# DriverBoard.net
KiCad netlist of a schematic drawn in EAGLE
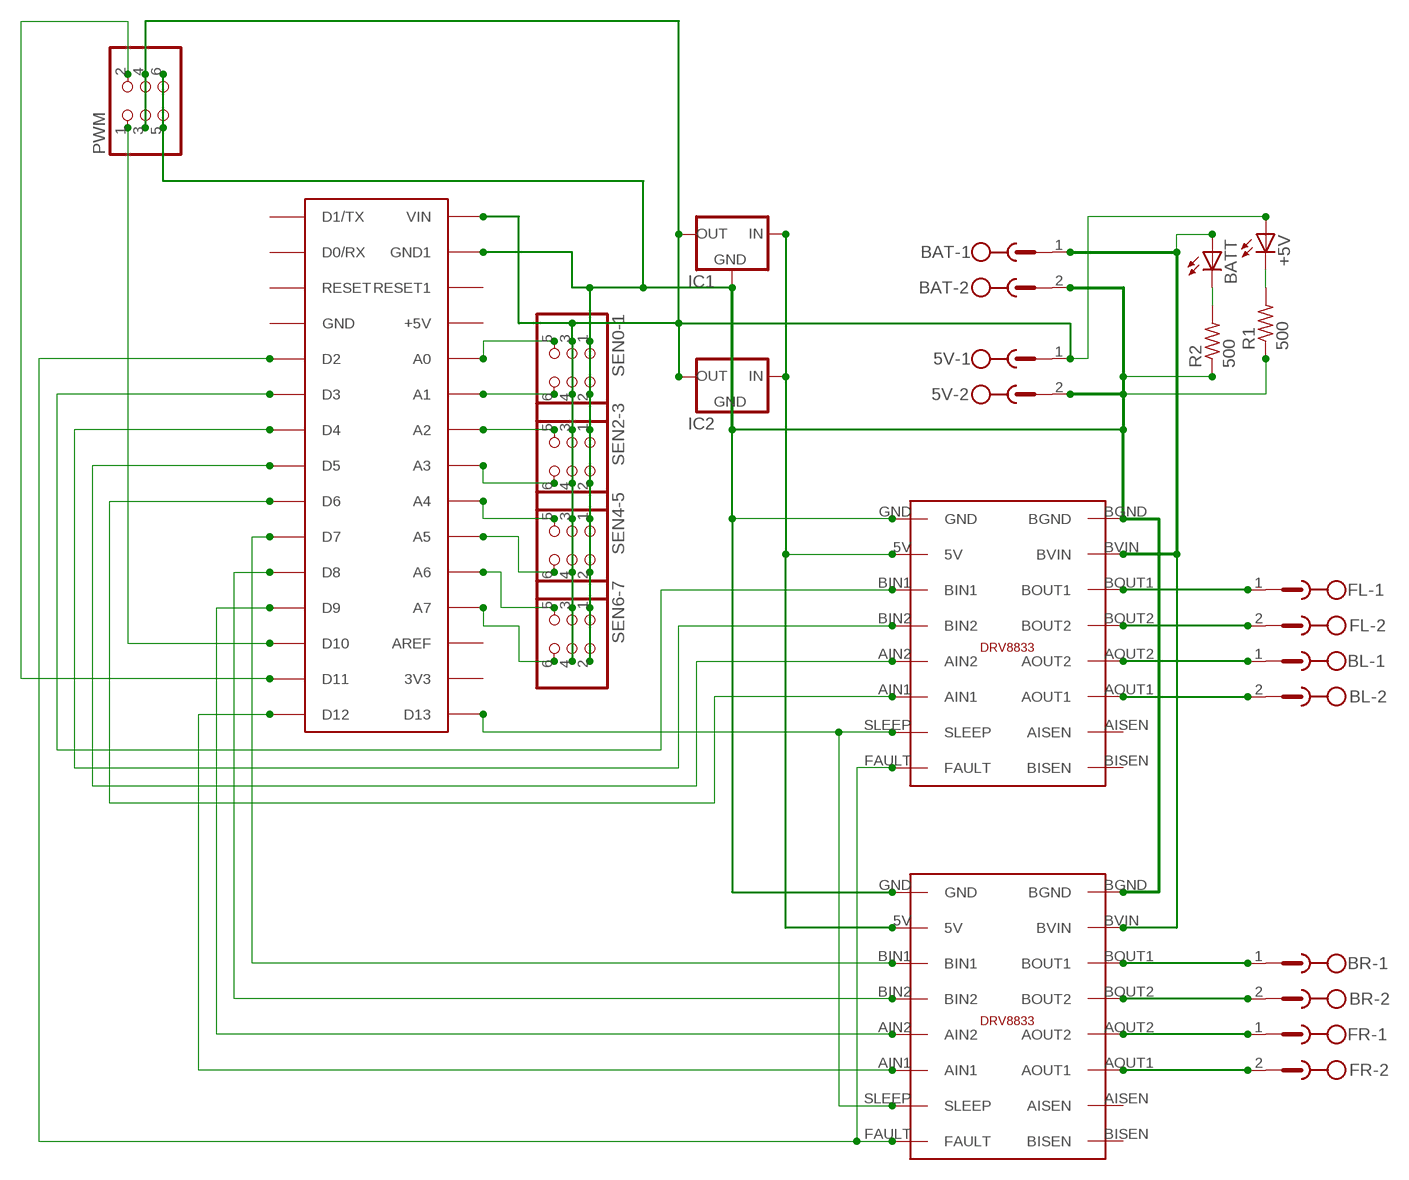
[diagram p0: schematic, sheet 1]

(export (version "E")
  (design (tool "Eeschema 10.0.6"))
  (components
    (comp (ref "+5V")
      (value "LED5MM")
      (footprint "eagle-import:LED5MM")
      (libsource (lib "eagle-import") (part "LED5MM"))
    )
    (comp (ref "5V")
      (value "MSTBV2")
      (footprint "eagle-import:MSTBV2")
      (libsource (lib "eagle-import") (part "MSTBV2"))
    )
    (comp (ref "BAT")
      (value "MSTBV2")
      (footprint "eagle-import:MSTBV2")
      (libsource (lib "eagle-import") (part "MSTBV2"))
    )
    (comp (ref "BATT")
      (value "LED5MM")
      (footprint "eagle-import:LED5MM")
      (libsource (lib "eagle-import") (part "LED5MM"))
    )
    (comp (ref "BL")
      (value "MSTBV2")
      (footprint "eagle-import:MSTBV2")
      (libsource (lib "eagle-import") (part "MSTBV2"))
    )
    (comp (ref "BR")
      (value "MSTBV2")
      (footprint "eagle-import:MSTBV2")
      (libsource (lib "eagle-import") (part "MSTBV2"))
    )
    (comp (ref "FL")
      (value "MSTBV2")
      (footprint "eagle-import:MSTBV2")
      (libsource (lib "eagle-import") (part "MSTBV2"))
    )
    (comp (ref "FR")
      (value "MSTBV2")
      (footprint "eagle-import:MSTBV2")
      (libsource (lib "eagle-import") (part "MSTBV2"))
    )
    (comp (ref "IC1")
      (value "78XXS")
      (footprint "eagle-import:78XXS")
      (libsource (lib "eagle-import") (part "78XXS"))
    )
    (comp (ref "IC2")
      (value "78XXS")
      (footprint "eagle-import:78XXS")
      (libsource (lib "eagle-import") (part "78XXS"))
    )
    (comp (ref "PWM")
      (value "PINHD-2X3")
      (footprint "eagle-import:2X03")
      (libsource (lib "eagle-import") (part "PINHD-2X3"))
    )
    (comp (ref "R1")
      (value "500")
      (footprint "eagle-import:0207_10")
      (libsource (lib "eagle-import") (part "R-US_0207/10"))
    )
    (comp (ref "R2")
      (value "500")
      (footprint "eagle-import:0207_10")
      (libsource (lib "eagle-import") (part "R-US_0207/10"))
    )
    (comp (ref "SEN0-1")
      (value "PINHD-2X3")
      (footprint "eagle-import:2X03")
      (libsource (lib "eagle-import") (part "PINHD-2X3"))
    )
    (comp (ref "SEN2-3")
      (value "PINHD-2X3")
      (footprint "eagle-import:2X03")
      (libsource (lib "eagle-import") (part "PINHD-2X3"))
    )
    (comp (ref "SEN4-5")
      (value "PINHD-2X3")
      (footprint "eagle-import:2X03")
      (libsource (lib "eagle-import") (part "PINHD-2X3"))
    )
    (comp (ref "SEN6-7")
      (value "PINHD-2X3")
      (footprint "eagle-import:2X03")
      (libsource (lib "eagle-import") (part "PINHD-2X3"))
    )
    (comp (ref "U$1")
      (value "ARDUINONANO")
      (footprint "eagle-import:PDIP-32")
      (libsource (lib "eagle-import") (part "ARDUINONANO"))
    )
    (comp (ref "U$2")
      (value "DRV8833")
      (footprint "eagle-import:DRV8833")
      (libsource (lib "eagle-import") (part "DRV8833"))
    )
    (comp (ref "U$3")
      (value "DRV8833")
      (footprint "eagle-import:DRV8833")
      (libsource (lib "eagle-import") (part "DRV8833"))
    )
  )
  (nets
    (net (code "1") (name "Net-(+5V-C)") (class "Default")
      (node (ref "+5V") (pin "K") (pinfunction "C_K") (pintype "passive"))
      (node (ref "R1") (pin "2") (pinfunction "2_2") (pintype "passive"))
    )
    (net (code "2") (name "Net-(5VA-SK)") (class "Default")
      (node (ref "+5V") (pin "A") (pinfunction "A_A") (pintype "passive"))
      (node (ref "5V") (pin "1") (pinfunction "SK_1") (pintype "passive"))
      (node (ref "IC1") (pin "OUT") (pinfunction "OUT_OUT") (pintype "passive"))
      (node (ref "IC2") (pin "OUT") (pinfunction "OUT_OUT") (pintype "passive"))
      (node (ref "PWM") (pin "3") (pinfunction "3_3") (pintype "passive"))
      (node (ref "PWM") (pin "4") (pinfunction "4_4") (pintype "passive"))
      (node (ref "SEN0-1") (pin "3") (pinfunction "3_3") (pintype "passive"))
      (node (ref "SEN0-1") (pin "4") (pinfunction "4_4") (pintype "passive"))
      (node (ref "SEN2-3") (pin "3") (pinfunction "3_3") (pintype "passive"))
      (node (ref "SEN2-3") (pin "4") (pinfunction "4_4") (pintype "passive"))
      (node (ref "SEN4-5") (pin "3") (pinfunction "3_3") (pintype "passive"))
      (node (ref "SEN4-5") (pin "4") (pinfunction "4_4") (pintype "passive"))
      (node (ref "SEN6-7") (pin "3") (pinfunction "3_3") (pintype "passive"))
      (node (ref "SEN6-7") (pin "4") (pinfunction "4_4") (pintype "passive"))
      (node (ref "U$1") (pin "VIN") (pinfunction "VIN_VIN") (pintype "bidirectional"))
    )
    (net (code "3") (name "Net-(5VB-SK)") (class "Default")
      (node (ref "5V") (pin "2") (pinfunction "SK_2") (pintype "passive"))
      (node (ref "BAT") (pin "2") (pinfunction "SK_2") (pintype "passive"))
      (node (ref "IC1") (pin "GND") (pinfunction "GND_GND") (pintype "input"))
      (node (ref "IC2") (pin "GND") (pinfunction "GND_GND") (pintype "input"))
      (node (ref "PWM") (pin "5") (pinfunction "5_5") (pintype "passive"))
      (node (ref "PWM") (pin "6") (pinfunction "6_6") (pintype "passive"))
      (node (ref "R1") (pin "1") (pinfunction "1_1") (pintype "passive"))
      (node (ref "R2") (pin "1") (pinfunction "1_1") (pintype "passive"))
      (node (ref "SEN0-1") (pin "1") (pinfunction "1_1") (pintype "passive"))
      (node (ref "SEN0-1") (pin "2") (pinfunction "2_2") (pintype "passive"))
      (node (ref "SEN2-3") (pin "1") (pinfunction "1_1") (pintype "passive"))
      (node (ref "SEN2-3") (pin "2") (pinfunction "2_2") (pintype "passive"))
      (node (ref "SEN4-5") (pin "1") (pinfunction "1_1") (pintype "passive"))
      (node (ref "SEN4-5") (pin "2") (pinfunction "2_2") (pintype "passive"))
      (node (ref "SEN6-7") (pin "1") (pinfunction "1_1") (pintype "passive"))
      (node (ref "SEN6-7") (pin "2") (pinfunction "2_2") (pintype "passive"))
      (node (ref "U$1") (pin "GND1") (pinfunction "GND1_GND1") (pintype "bidirectional"))
      (node (ref "U$2") (pin "BGND") (pinfunction "BGND_BGND") (pintype "bidirectional"))
      (node (ref "U$2") (pin "GND") (pinfunction "GND_GND") (pintype "bidirectional"))
      (node (ref "U$3") (pin "BGND") (pinfunction "BGND_BGND") (pintype "bidirectional"))
      (node (ref "U$3") (pin "GND") (pinfunction "GND_GND") (pintype "bidirectional"))
    )
    (net (code "4") (name "Net-(BATA-SK)") (class "Default")
      (node (ref "BAT") (pin "1") (pinfunction "SK_1") (pintype "passive"))
      (node (ref "BATT") (pin "A") (pinfunction "A_A") (pintype "passive"))
      (node (ref "U$2") (pin "BVIN") (pinfunction "BVIN_BVIN") (pintype "bidirectional"))
      (node (ref "U$3") (pin "BVIN") (pinfunction "BVIN_BVIN") (pintype "bidirectional"))
    )
    (net (code "5") (name "Net-(BATT-C)") (class "Default")
      (node (ref "BATT") (pin "K") (pinfunction "C_K") (pintype "passive"))
      (node (ref "R2") (pin "2") (pinfunction "2_2") (pintype "passive"))
    )
    (net (code "6") (name "Net-(BLA-SK)") (class "Default")
      (node (ref "BL") (pin "1") (pinfunction "SK_1") (pintype "passive"))
      (node (ref "U$2") (pin "AOUT2") (pinfunction "AOUT2_AOUT2") (pintype "bidirectional"))
    )
    (net (code "7") (name "Net-(BLB-SK)") (class "Default")
      (node (ref "BL") (pin "2") (pinfunction "SK_2") (pintype "passive"))
      (node (ref "U$2") (pin "AOUT1") (pinfunction "AOUT1_AOUT1") (pintype "bidirectional"))
    )
    (net (code "8") (name "Net-(BRA-SK)") (class "Default")
      (node (ref "BR") (pin "1") (pinfunction "SK_1") (pintype "passive"))
      (node (ref "U$3") (pin "BOUT1") (pinfunction "BOUT1_BOUT1") (pintype "bidirectional"))
    )
    (net (code "9") (name "Net-(BRB-SK)") (class "Default")
      (node (ref "BR") (pin "2") (pinfunction "SK_2") (pintype "passive"))
      (node (ref "U$3") (pin "BOUT2") (pinfunction "BOUT2_BOUT2") (pintype "bidirectional"))
    )
    (net (code "10") (name "Net-(FLA-SK)") (class "Default")
      (node (ref "FL") (pin "1") (pinfunction "SK_1") (pintype "passive"))
      (node (ref "U$2") (pin "BOUT1") (pinfunction "BOUT1_BOUT1") (pintype "bidirectional"))
    )
    (net (code "11") (name "Net-(FLB-SK)") (class "Default")
      (node (ref "FL") (pin "2") (pinfunction "SK_2") (pintype "passive"))
      (node (ref "U$2") (pin "BOUT2") (pinfunction "BOUT2_BOUT2") (pintype "bidirectional"))
    )
    (net (code "12") (name "Net-(FRA-SK)") (class "Default")
      (node (ref "FR") (pin "1") (pinfunction "SK_1") (pintype "passive"))
      (node (ref "U$3") (pin "AOUT2") (pinfunction "AOUT2_AOUT2") (pintype "bidirectional"))
    )
    (net (code "13") (name "Net-(FRB-SK)") (class "Default")
      (node (ref "FR") (pin "2") (pinfunction "SK_2") (pintype "passive"))
      (node (ref "U$3") (pin "AOUT1") (pinfunction "AOUT1_AOUT1") (pintype "bidirectional"))
    )
    (net (code "14") (name "Net-(IC1-PadIN)") (class "Default")
      (node (ref "IC1") (pin "IN") (pinfunction "IN_IN") (pintype "input"))
      (node (ref "IC2") (pin "IN") (pinfunction "IN_IN") (pintype "input"))
      (node (ref "U$2") (pin "5V") (pinfunction "5V_5V") (pintype "bidirectional"))
      (node (ref "U$3") (pin "5V") (pinfunction "5V_5V") (pintype "bidirectional"))
    )
    (net (code "15") (name "Net-(PWM-Pad1)") (class "Default")
      (node (ref "PWM") (pin "1") (pinfunction "1_1") (pintype "passive"))
      (node (ref "U$1") (pin "D10") (pinfunction "D10_D10") (pintype "bidirectional"))
    )
    (net (code "16") (name "Net-(PWM-Pad2)") (class "Default")
      (node (ref "PWM") (pin "2") (pinfunction "2_2") (pintype "passive"))
      (node (ref "U$1") (pin "D11") (pinfunction "D11_D11") (pintype "bidirectional"))
    )
    (net (code "17") (name "Net-(SEN0-1-Pad5)") (class "Default")
      (node (ref "SEN0-1") (pin "5") (pinfunction "5_5") (pintype "passive"))
      (node (ref "U$1") (pin "A0") (pinfunction "A0_A0") (pintype "bidirectional"))
    )
    (net (code "18") (name "Net-(SEN0-1-Pad6)") (class "Default")
      (node (ref "SEN0-1") (pin "6") (pinfunction "6_6") (pintype "passive"))
      (node (ref "U$1") (pin "A1") (pinfunction "A1_A1") (pintype "bidirectional"))
    )
    (net (code "19") (name "Net-(SEN2-3-Pad5)") (class "Default")
      (node (ref "SEN2-3") (pin "5") (pinfunction "5_5") (pintype "passive"))
      (node (ref "U$1") (pin "A2") (pinfunction "A2_A2") (pintype "bidirectional"))
    )
    (net (code "20") (name "Net-(SEN2-3-Pad6)") (class "Default")
      (node (ref "SEN2-3") (pin "6") (pinfunction "6_6") (pintype "passive"))
      (node (ref "U$1") (pin "A3") (pinfunction "A3_A3") (pintype "bidirectional"))
    )
    (net (code "21") (name "Net-(SEN4-5-Pad5)") (class "Default")
      (node (ref "SEN4-5") (pin "5") (pinfunction "5_5") (pintype "passive"))
      (node (ref "U$1") (pin "A4") (pinfunction "A4_A4") (pintype "bidirectional"))
    )
    (net (code "22") (name "Net-(SEN4-5-Pad6)") (class "Default")
      (node (ref "SEN4-5") (pin "6") (pinfunction "6_6") (pintype "passive"))
      (node (ref "U$1") (pin "A5") (pinfunction "A5_A5") (pintype "bidirectional"))
    )
    (net (code "23") (name "Net-(SEN6-7-Pad5)") (class "Default")
      (node (ref "SEN6-7") (pin "5") (pinfunction "5_5") (pintype "passive"))
      (node (ref "U$1") (pin "A6") (pinfunction "A6_A6") (pintype "bidirectional"))
    )
    (net (code "24") (name "Net-(SEN6-7-Pad6)") (class "Default")
      (node (ref "SEN6-7") (pin "6") (pinfunction "6_6") (pintype "passive"))
      (node (ref "U$1") (pin "A7") (pinfunction "A7_A7") (pintype "bidirectional"))
    )
    (net (code "25") (name "Net-(U$1-PadD2)") (class "Default")
      (node (ref "U$1") (pin "D2") (pinfunction "D2_D2") (pintype "bidirectional"))
      (node (ref "U$2") (pin "FAULT") (pinfunction "FAULT_FAULT") (pintype "bidirectional"))
      (node (ref "U$3") (pin "FAULT") (pinfunction "FAULT_FAULT") (pintype "bidirectional"))
    )
    (net (code "26") (name "Net-(U$1-PadD3)") (class "Default")
      (node (ref "U$1") (pin "D3") (pinfunction "D3_D3") (pintype "bidirectional"))
      (node (ref "U$2") (pin "BIN1") (pinfunction "BIN1_BIN1") (pintype "bidirectional"))
    )
    (net (code "27") (name "Net-(U$1-PadD4)") (class "Default")
      (node (ref "U$1") (pin "D4") (pinfunction "D4_D4") (pintype "bidirectional"))
      (node (ref "U$2") (pin "BIN2") (pinfunction "BIN2_BIN2") (pintype "bidirectional"))
    )
    (net (code "28") (name "Net-(U$1-PadD5)") (class "Default")
      (node (ref "U$1") (pin "D5") (pinfunction "D5_D5") (pintype "bidirectional"))
      (node (ref "U$2") (pin "AIN2") (pinfunction "AIN2_AIN2") (pintype "bidirectional"))
    )
    (net (code "29") (name "Net-(U$1-PadD6)") (class "Default")
      (node (ref "U$1") (pin "D6") (pinfunction "D6_D6") (pintype "bidirectional"))
      (node (ref "U$2") (pin "AIN1") (pinfunction "AIN1_AIN1") (pintype "bidirectional"))
    )
    (net (code "30") (name "Net-(U$1-PadD7)") (class "Default")
      (node (ref "U$1") (pin "D7") (pinfunction "D7_D7") (pintype "bidirectional"))
      (node (ref "U$3") (pin "BIN1") (pinfunction "BIN1_BIN1") (pintype "bidirectional"))
    )
    (net (code "31") (name "Net-(U$1-PadD8)") (class "Default")
      (node (ref "U$1") (pin "D8") (pinfunction "D8_D8") (pintype "bidirectional"))
      (node (ref "U$3") (pin "BIN2") (pinfunction "BIN2_BIN2") (pintype "bidirectional"))
    )
    (net (code "32") (name "Net-(U$1-PadD9)") (class "Default")
      (node (ref "U$1") (pin "D9") (pinfunction "D9_D9") (pintype "bidirectional"))
      (node (ref "U$3") (pin "AIN2") (pinfunction "AIN2_AIN2") (pintype "bidirectional"))
    )
    (net (code "33") (name "Net-(U$1-PadD12)") (class "Default")
      (node (ref "U$1") (pin "D12") (pinfunction "D12_D12") (pintype "bidirectional"))
      (node (ref "U$3") (pin "AIN1") (pinfunction "AIN1_AIN1") (pintype "bidirectional"))
    )
    (net (code "34") (name "Net-(U$1-PadD13)") (class "Default")
      (node (ref "U$1") (pin "D13") (pinfunction "D13_D13") (pintype "bidirectional"))
      (node (ref "U$2") (pin "SLEEP") (pinfunction "SLEEP_SLEEP") (pintype "bidirectional"))
      (node (ref "U$3") (pin "SLEEP") (pinfunction "SLEEP_SLEEP") (pintype "bidirectional"))
    )
    (net (code "35") (name "unconnected-(U$1-Pad+5V)") (class "Default")
      (node (ref "U$1") (pin "+5V") (pinfunction "+5V_+5V") (pintype "bidirectional"))
    )
    (net (code "36") (name "unconnected-(U$1-Pad3V3)") (class "Default")
      (node (ref "U$1") (pin "3V3") (pinfunction "3V3_3V3") (pintype "bidirectional"))
    )
    (net (code "37") (name "unconnected-(U$1-PadAREF)") (class "Default")
      (node (ref "U$1") (pin "AREF") (pinfunction "AREF_AREF") (pintype "bidirectional"))
    )
    (net (code "38") (name "unconnected-(U$1-PadD0{slash}RX)") (class "Default")
      (node (ref "U$1") (pin "D0/RX") (pinfunction "D0/RX_D0/RX") (pintype "bidirectional"))
    )
    (net (code "39") (name "unconnected-(U$1-PadD1{slash}TX)") (class "Default")
      (node (ref "U$1") (pin "D1/TX") (pinfunction "D1/TX_D1/TX") (pintype "bidirectional"))
    )
    (net (code "40") (name "unconnected-(U$1-PadGND)") (class "Default")
      (node (ref "U$1") (pin "GND") (pinfunction "GND_GND") (pintype "bidirectional"))
    )
    (net (code "41") (name "unconnected-(U$1-PadRESET)") (class "Default")
      (node (ref "U$1") (pin "RESET") (pinfunction "RESET_RESET") (pintype "bidirectional"))
    )
    (net (code "42") (name "unconnected-(U$1-PadRESET1)") (class "Default")
      (node (ref "U$1") (pin "RESET1") (pinfunction "RESET1_RESET1") (pintype "bidirectional"))
    )
    (net (code "43") (name "unconnected-(U$2-PadAISEN)") (class "Default")
      (node (ref "U$2") (pin "AISEN") (pinfunction "AISEN_AISEN") (pintype "bidirectional"))
    )
    (net (code "44") (name "unconnected-(U$2-PadBISEN)") (class "Default")
      (node (ref "U$2") (pin "BISEN") (pinfunction "BISEN_BISEN") (pintype "bidirectional"))
    )
    (net (code "45") (name "unconnected-(U$3-PadAISEN)") (class "Default")
      (node (ref "U$3") (pin "AISEN") (pinfunction "AISEN_AISEN") (pintype "bidirectional"))
    )
    (net (code "46") (name "unconnected-(U$3-PadBISEN)") (class "Default")
      (node (ref "U$3") (pin "BISEN") (pinfunction "BISEN_BISEN") (pintype "bidirectional"))
    )
  )
)
